# DM0250_Power.net
KiCad netlist of a schematic drawn in Altium Designer
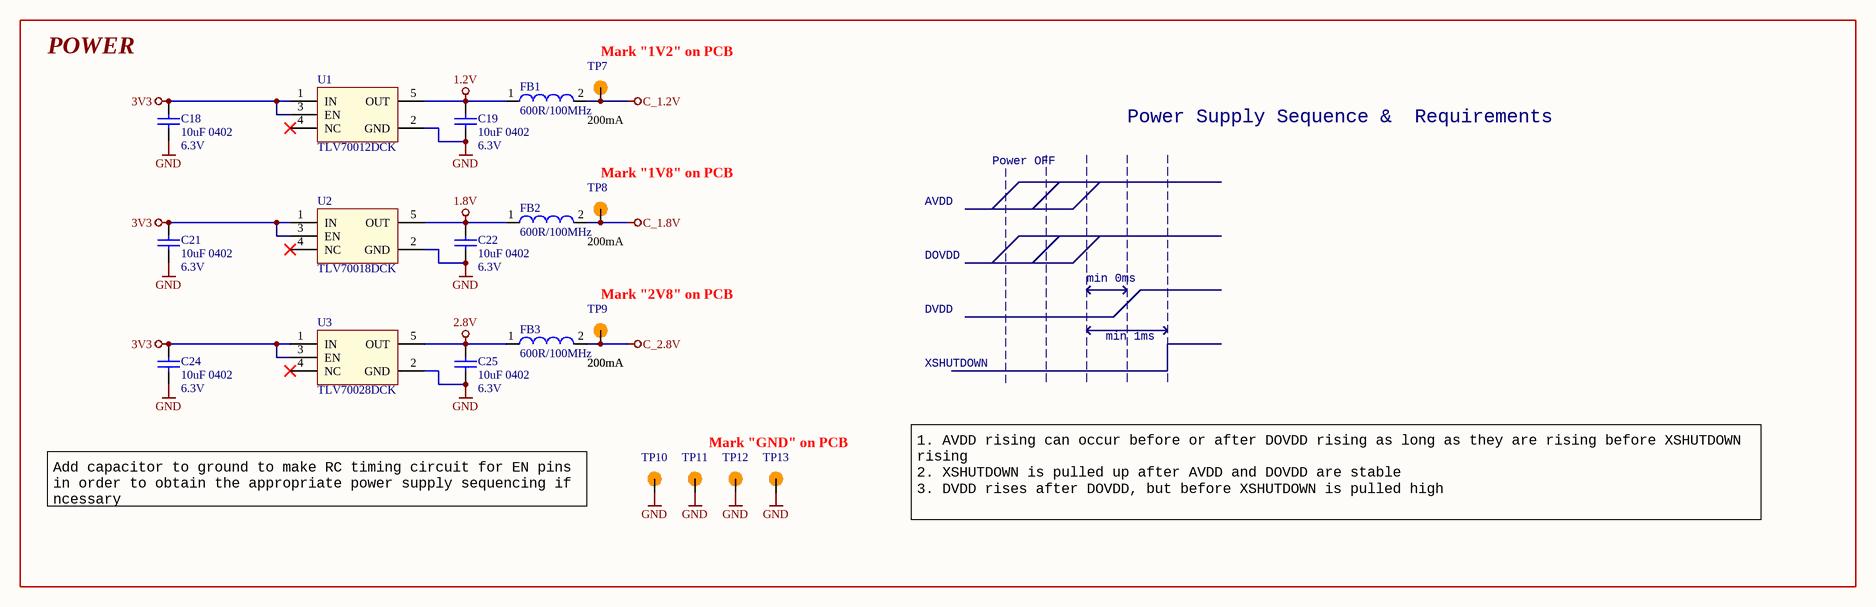
[diagram p0: DM0250_Power.SchDoc]

(export (version "E")
  (design (tool "Eeschema 10.0.6"))
  (components
    (comp (ref "C18")
      (value "10uF 0402")
      (footprint "CAP_Altium_Vault_Generic:CAPC0402(1005)70_N")
      (description "CAP CER 10UF 6.3V X5R 0402 20%")
      (fields (field (name "TOLERANCE") "20%") (field (name "VOLTAGE RATING") "6.3V"))
      (libsource (lib "LuxonisMaster") (part "GRM155R60J106ME15D"))
    )
    (comp (ref "C19")
      (value "10uF 0402")
      (footprint "CAP_Altium_Vault_Generic:CAPC0402(1005)70_N")
      (description "CAP CER 10UF 6.3V X5R 0402 20%")
      (fields (field (name "TOLERANCE") "20%") (field (name "VOLTAGE RATING") "6.3V"))
      (libsource (lib "LuxonisMaster") (part "GRM155R60J106ME15D"))
    )
    (comp (ref "C21")
      (value "10uF 0402")
      (footprint "CAP_Altium_Vault_Generic:CAPC0402(1005)70_N")
      (description "CAP CER 10UF 6.3V X5R 0402 20%")
      (fields (field (name "TOLERANCE") "20%") (field (name "VOLTAGE RATING") "6.3V"))
      (libsource (lib "LuxonisMaster") (part "GRM155R60J106ME15D"))
    )
    (comp (ref "C22")
      (value "10uF 0402")
      (footprint "CAP_Altium_Vault_Generic:CAPC0402(1005)70_N")
      (description "CAP CER 10UF 6.3V X5R 0402 20%")
      (fields (field (name "TOLERANCE") "20%") (field (name "VOLTAGE RATING") "6.3V"))
      (libsource (lib "LuxonisMaster") (part "GRM155R60J106ME15D"))
    )
    (comp (ref "C24")
      (value "10uF 0402")
      (footprint "CAP_Altium_Vault_Generic:CAPC0402(1005)70_N")
      (description "CAP CER 10UF 6.3V X5R 0402 20%")
      (fields (field (name "TOLERANCE") "20%") (field (name "VOLTAGE RATING") "6.3V"))
      (libsource (lib "LuxonisMaster") (part "GRM155R60J106ME15D"))
    )
    (comp (ref "C25")
      (value "10uF 0402")
      (footprint "CAP_Altium_Vault_Generic:CAPC0402(1005)70_N")
      (description "CAP CER 10UF 6.3V X5R 0402 20%")
      (fields (field (name "TOLERANCE") "20%") (field (name "VOLTAGE RATING") "6.3V"))
      (libsource (lib "LuxonisMaster") (part "GRM155R60J106ME15D"))
    )
    (comp (ref "FB1")
      (value "600R/100MHz")
      (footprint "LuxonisMaster:2508056017Y2")
      (description "FERRITE BEAD, 0.1OHM, 2A, 0805, 600R/100MHz")
      (fields (field (name "TOLERANCE") "25%"))
      (libsource (lib "LuxonisMaster") (part "2508056017Y2"))
    )
    (comp (ref "FB2")
      (value "600R/100MHz")
      (footprint "LuxonisMaster:2508056017Y2")
      (description "FERRITE BEAD, 0.1OHM, 2A, 0805, 600R/100MHz")
      (fields (field (name "TOLERANCE") "25%"))
      (libsource (lib "LuxonisMaster") (part "2508056017Y2"))
    )
    (comp (ref "FB3")
      (value "600R/100MHz")
      (footprint "LuxonisMaster:2508056017Y2")
      (description "FERRITE BEAD, 0.1OHM, 2A, 0805, 600R/100MHz")
      (fields (field (name "TOLERANCE") "25%"))
      (libsource (lib "LuxonisMaster") (part "2508056017Y2"))
    )
    (comp (ref "TP7")
      (value "TP100_150_NS")
      (footprint "LuxonisMaster:TP100_150_NS")
      (libsource (lib "LuxonisMaster") (part "TEST_POINT"))
    )
    (comp (ref "TP8")
      (value "TP100_150_NS")
      (footprint "LuxonisMaster:TP100_150_NS")
      (libsource (lib "LuxonisMaster") (part "TEST_POINT"))
    )
    (comp (ref "TP9")
      (value "TP100_150_NS")
      (footprint "LuxonisMaster:TP100_150_NS")
      (libsource (lib "LuxonisMaster") (part "TEST_POINT"))
    )
    (comp (ref "TP10")
      (value "TP100_150_NS")
      (footprint "LuxonisMaster:TP100_150_NS")
      (libsource (lib "LuxonisMaster") (part "TEST_POINT"))
    )
    (comp (ref "TP11")
      (value "TP100_150_NS")
      (footprint "LuxonisMaster:TP100_150_NS")
      (libsource (lib "LuxonisMaster") (part "TEST_POINT"))
    )
    (comp (ref "TP12")
      (value "TP100_150_NS")
      (footprint "LuxonisMaster:TP100_150_NS")
      (libsource (lib "LuxonisMaster") (part "TEST_POINT"))
    )
    (comp (ref "TP13")
      (value "TP100_150_NS")
      (footprint "LuxonisMaster:TP100_150_NS")
      (libsource (lib "LuxonisMaster") (part "TEST_POINT"))
    )
    (comp (ref "U1")
      (value "TLV70012DCK")
      (footprint "LuxonisMaster:TLV70012DCK")
      (description "IC REG LINEAR 1.2V 200MA SC70-5")
      (libsource (lib "LuxonisMaster") (part "TLV70012DCK"))
    )
    (comp (ref "U2")
      (value "TLV70018DCK")
      (footprint "LuxonisMaster:TLV70018DCK")
      (description "IC REG LINEAR 1.8V 200MA SC70-5 Linear Voltage Regulator IC  1 Output  200mA SC-70-5")
      (libsource (lib "LuxonisMaster") (part "TLV70018DCK"))
    )
    (comp (ref "U3")
      (value "TLV70028DCK")
      (footprint "LuxonisMaster:TLV70028DCK")
      (description "IC REG LINEAR 2.8V 200MA SC70-5 Linear Voltage Regulator IC  1 Output  200mA SC-70-5")
      (libsource (lib "LuxonisMaster") (part "TLV70028DCK"))
    )
  )
  (nets
    (net (code "1") (name "1.2V") (class "Default")
      (node (ref "C19") (pin "2") (pinfunction "2_2") (pintype "passive"))
      (node (ref "FB1") (pin "1") (pinfunction "1_1") (pintype "passive"))
      (node (ref "U1") (pin "5") (pinfunction "OUT_5") (pintype "passive"))
    )
    (net (code "2") (name "1.8V") (class "Default")
      (node (ref "C22") (pin "2") (pinfunction "2_2") (pintype "passive"))
      (node (ref "FB2") (pin "1") (pinfunction "1_1") (pintype "passive"))
      (node (ref "U2") (pin "5") (pinfunction "OUT_5") (pintype "passive"))
    )
    (net (code "3") (name "2.8V") (class "Default")
      (node (ref "C25") (pin "2") (pinfunction "2_2") (pintype "passive"))
      (node (ref "FB3") (pin "1") (pinfunction "1_1") (pintype "passive"))
      (node (ref "U3") (pin "5") (pinfunction "OUT_5") (pintype "passive"))
    )
    (net (code "4") (name "3V3") (class "Default")
      (node (ref "C18") (pin "2") (pinfunction "2_2") (pintype "passive"))
      (node (ref "C21") (pin "2") (pinfunction "2_2") (pintype "passive"))
      (node (ref "C24") (pin "2") (pinfunction "2_2") (pintype "passive"))
      (node (ref "U1") (pin "1") (pinfunction "IN_1") (pintype "passive"))
      (node (ref "U1") (pin "3") (pinfunction "EN_3") (pintype "passive"))
      (node (ref "U2") (pin "1") (pinfunction "IN_1") (pintype "passive"))
      (node (ref "U2") (pin "3") (pinfunction "EN_3") (pintype "passive"))
      (node (ref "U3") (pin "1") (pinfunction "IN_1") (pintype "passive"))
      (node (ref "U3") (pin "3") (pinfunction "EN_3") (pintype "passive"))
    )
    (net (code "5") (name "C_1.2V") (class "Default")
      (node (ref "FB1") (pin "2") (pinfunction "2_2") (pintype "passive"))
      (node (ref "TP7") (pin "1") (pintype "passive"))
    )
    (net (code "6") (name "C_1.8V") (class "Default")
      (node (ref "FB2") (pin "2") (pinfunction "2_2") (pintype "passive"))
      (node (ref "TP8") (pin "1") (pintype "passive"))
    )
    (net (code "7") (name "C_2.8V") (class "Default")
      (node (ref "FB3") (pin "2") (pinfunction "2_2") (pintype "passive"))
      (node (ref "TP9") (pin "1") (pintype "passive"))
    )
    (net (code "8") (name "GND") (class "Default")
      (node (ref "C18") (pin "1") (pinfunction "1_1") (pintype "passive"))
      (node (ref "C19") (pin "1") (pinfunction "1_1") (pintype "passive"))
      (node (ref "C21") (pin "1") (pinfunction "1_1") (pintype "passive"))
      (node (ref "C22") (pin "1") (pinfunction "1_1") (pintype "passive"))
      (node (ref "C24") (pin "1") (pinfunction "1_1") (pintype "passive"))
      (node (ref "C25") (pin "1") (pinfunction "1_1") (pintype "passive"))
      (node (ref "TP10") (pin "1") (pintype "passive"))
      (node (ref "TP11") (pin "1") (pintype "passive"))
      (node (ref "TP12") (pin "1") (pintype "passive"))
      (node (ref "TP13") (pin "1") (pintype "passive"))
      (node (ref "U1") (pin "2") (pinfunction "GND_2") (pintype "passive"))
      (node (ref "U2") (pin "2") (pinfunction "GND_2") (pintype "passive"))
      (node (ref "U3") (pin "2") (pinfunction "GND_2") (pintype "passive"))
    )
    (net (code "9") (name "unconnected-(U1-NC-Pad4)") (class "Default")
      (node (ref "U1") (pin "4") (pinfunction "NC_4") (pintype "passive+no_connect"))
    )
    (net (code "10") (name "unconnected-(U2-NC-Pad4)") (class "Default")
      (node (ref "U2") (pin "4") (pinfunction "NC_4") (pintype "passive+no_connect"))
    )
    (net (code "11") (name "unconnected-(U3-NC-Pad4)") (class "Default")
      (node (ref "U3") (pin "4") (pinfunction "NC_4") (pintype "passive+no_connect"))
    )
  )
)
